# baseboard_rev_01.net
KiCad netlist of a schematic drawn in EAGLE
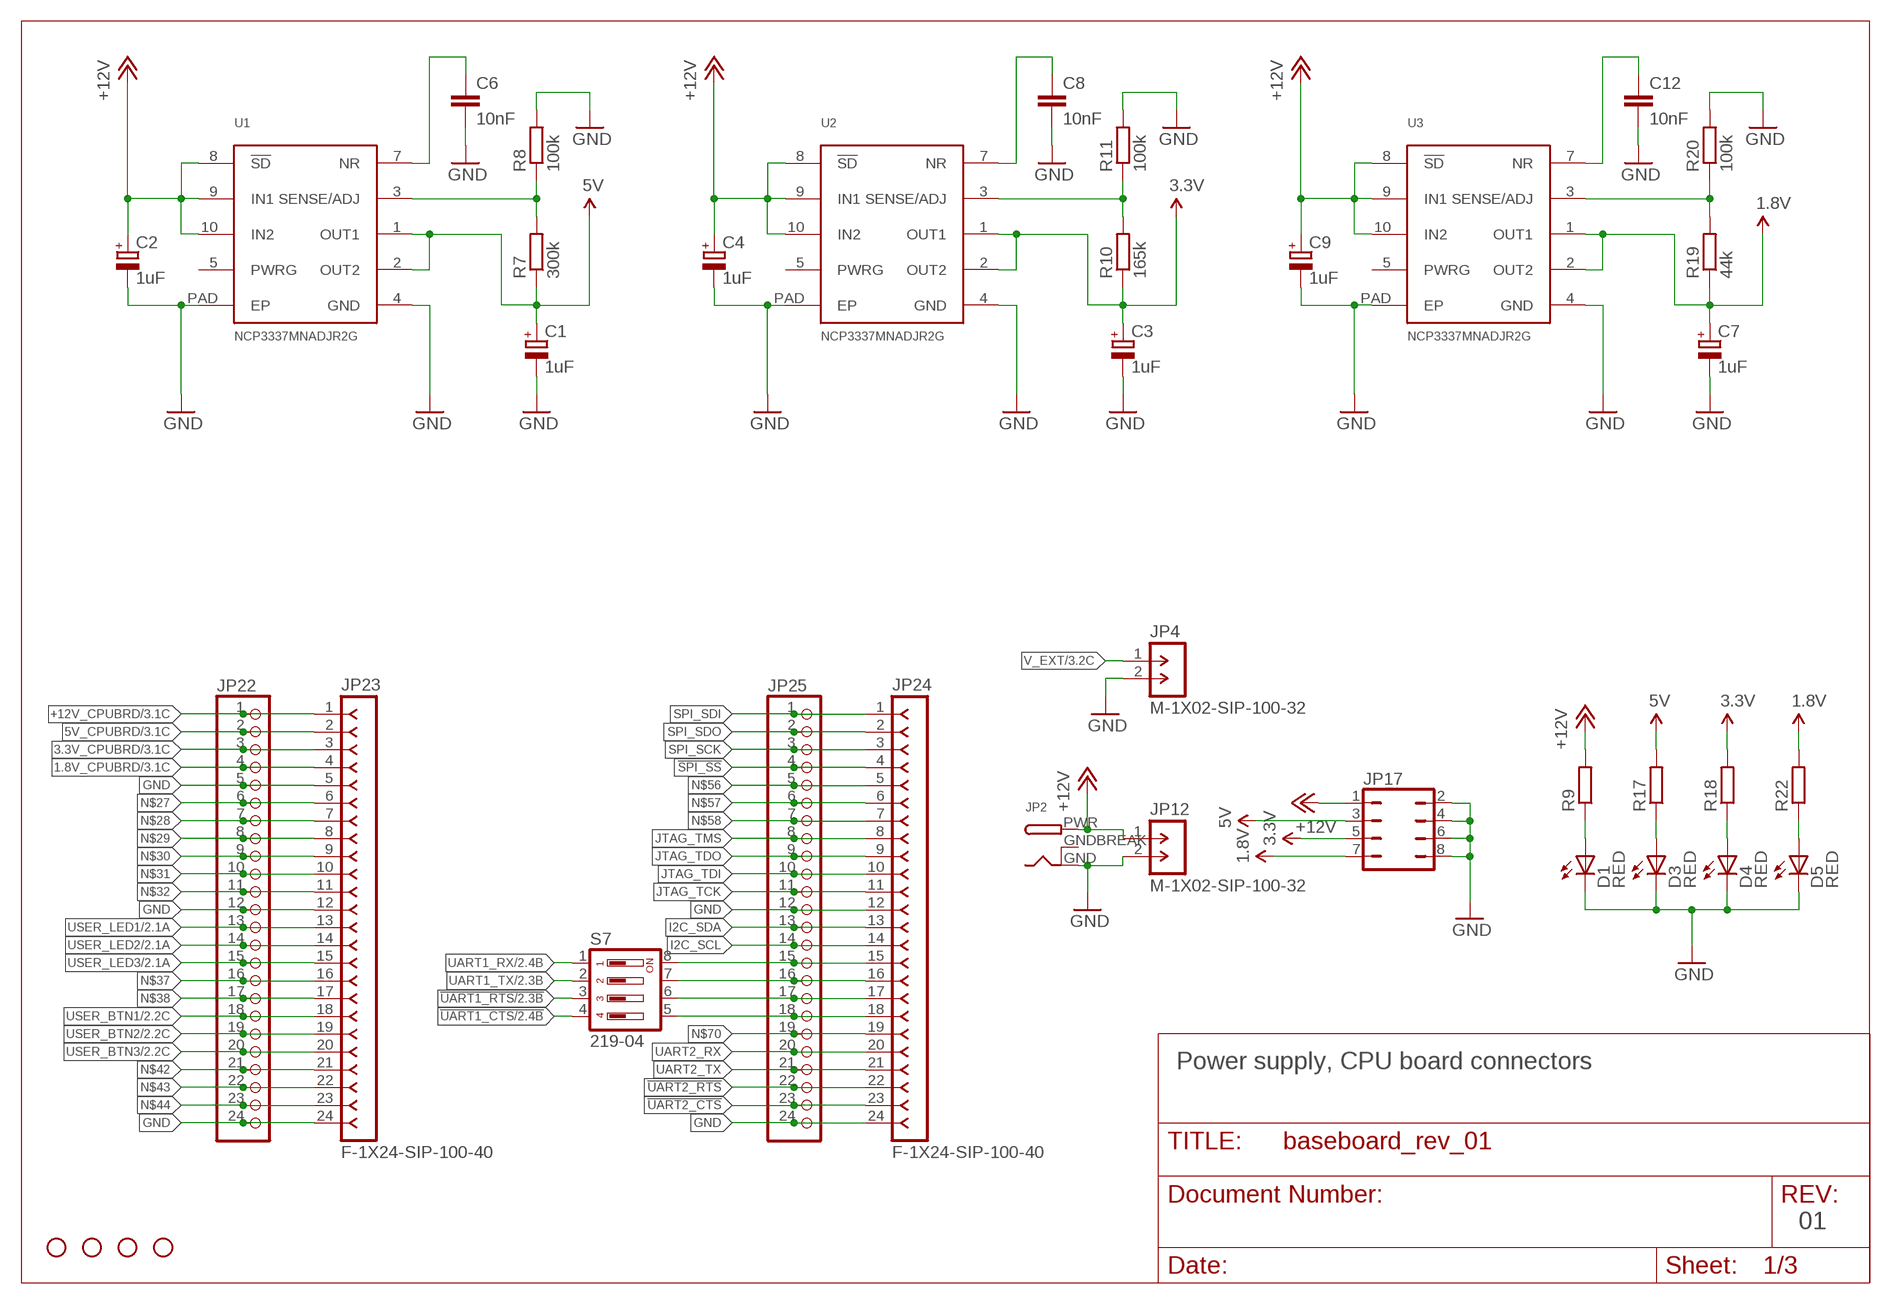
[diagram p0: schematic, sheet 1]
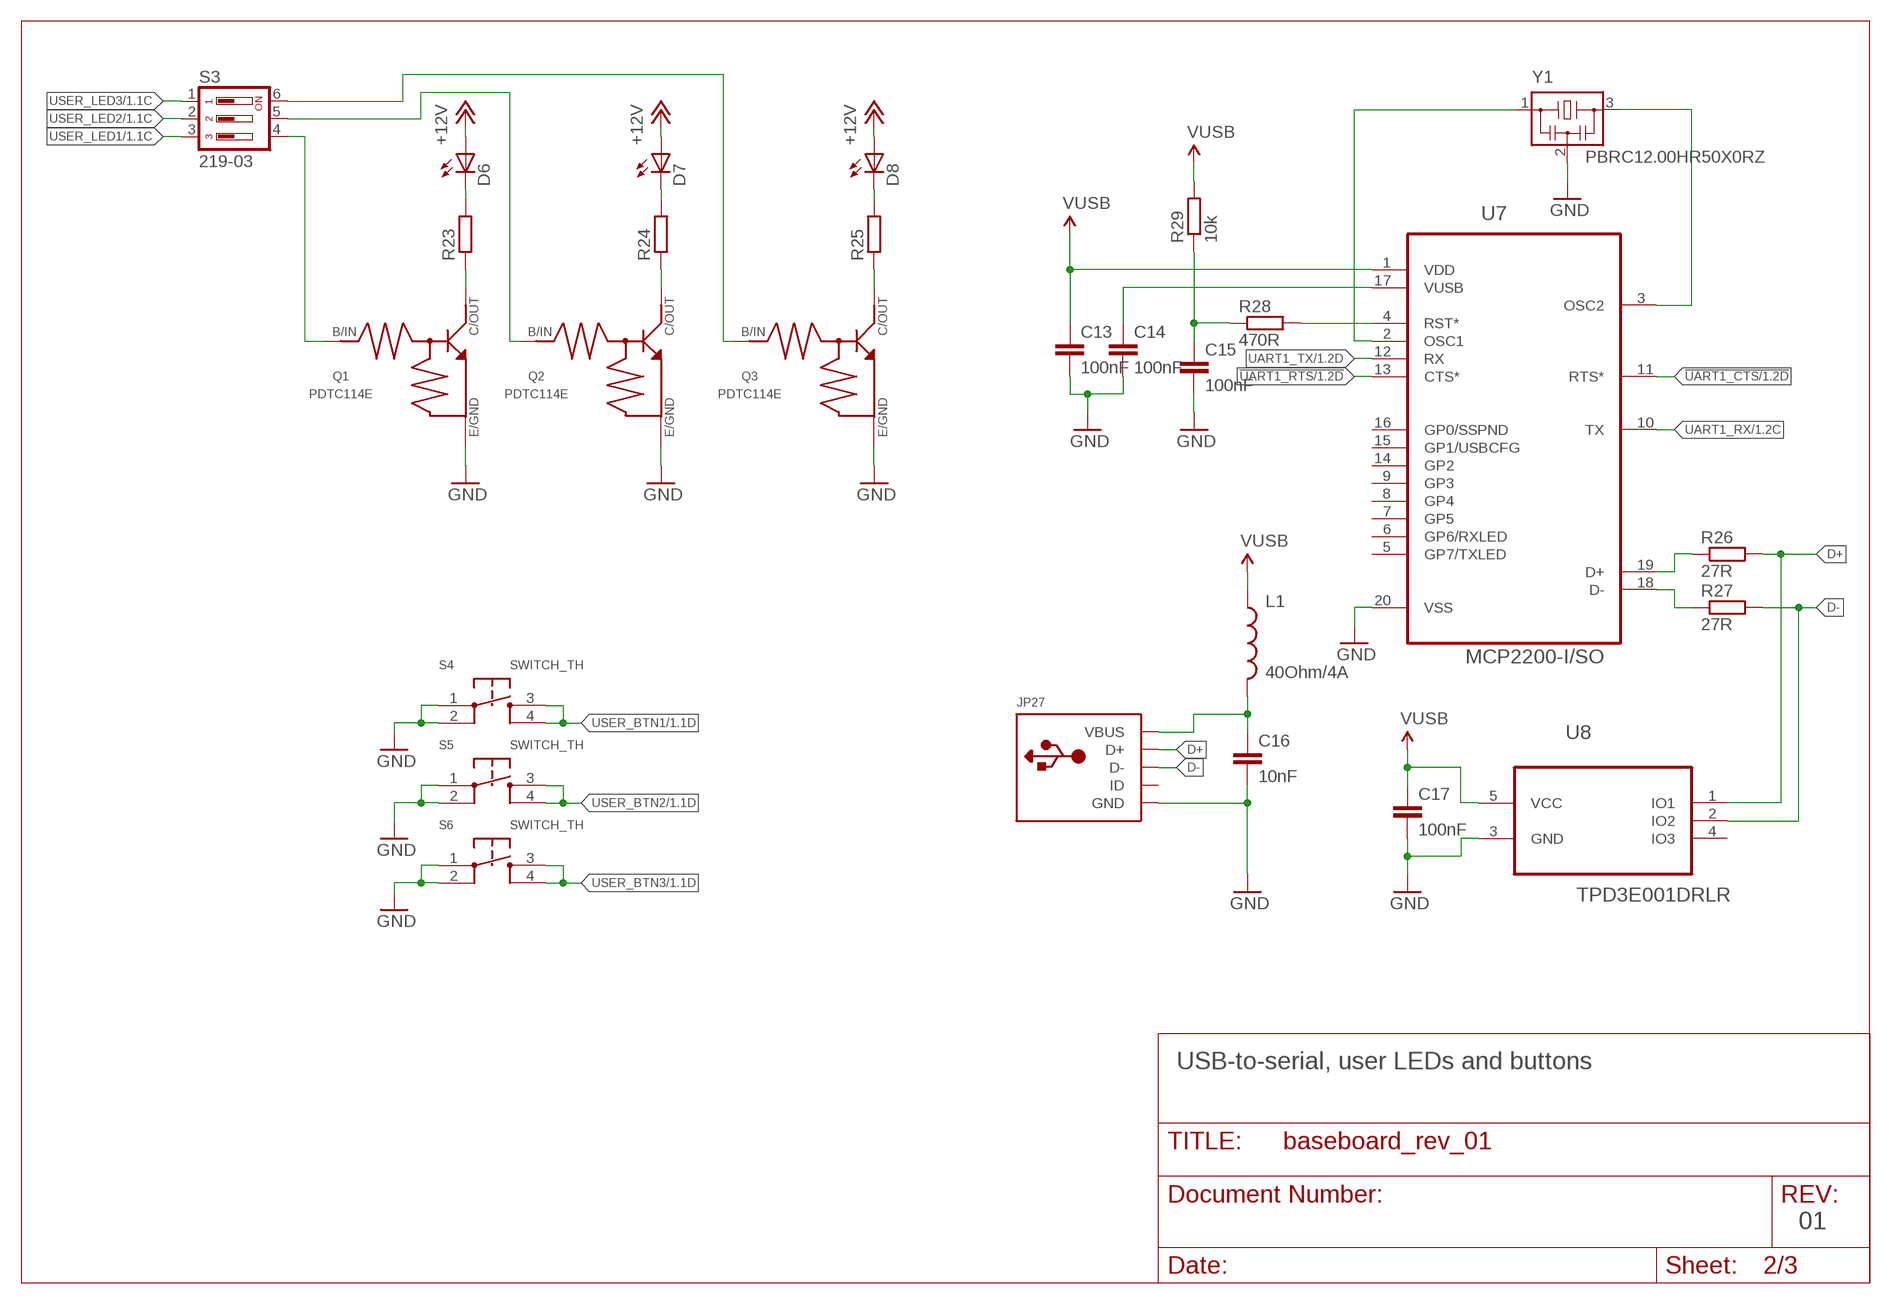
[diagram p1: schematic, sheet 2]
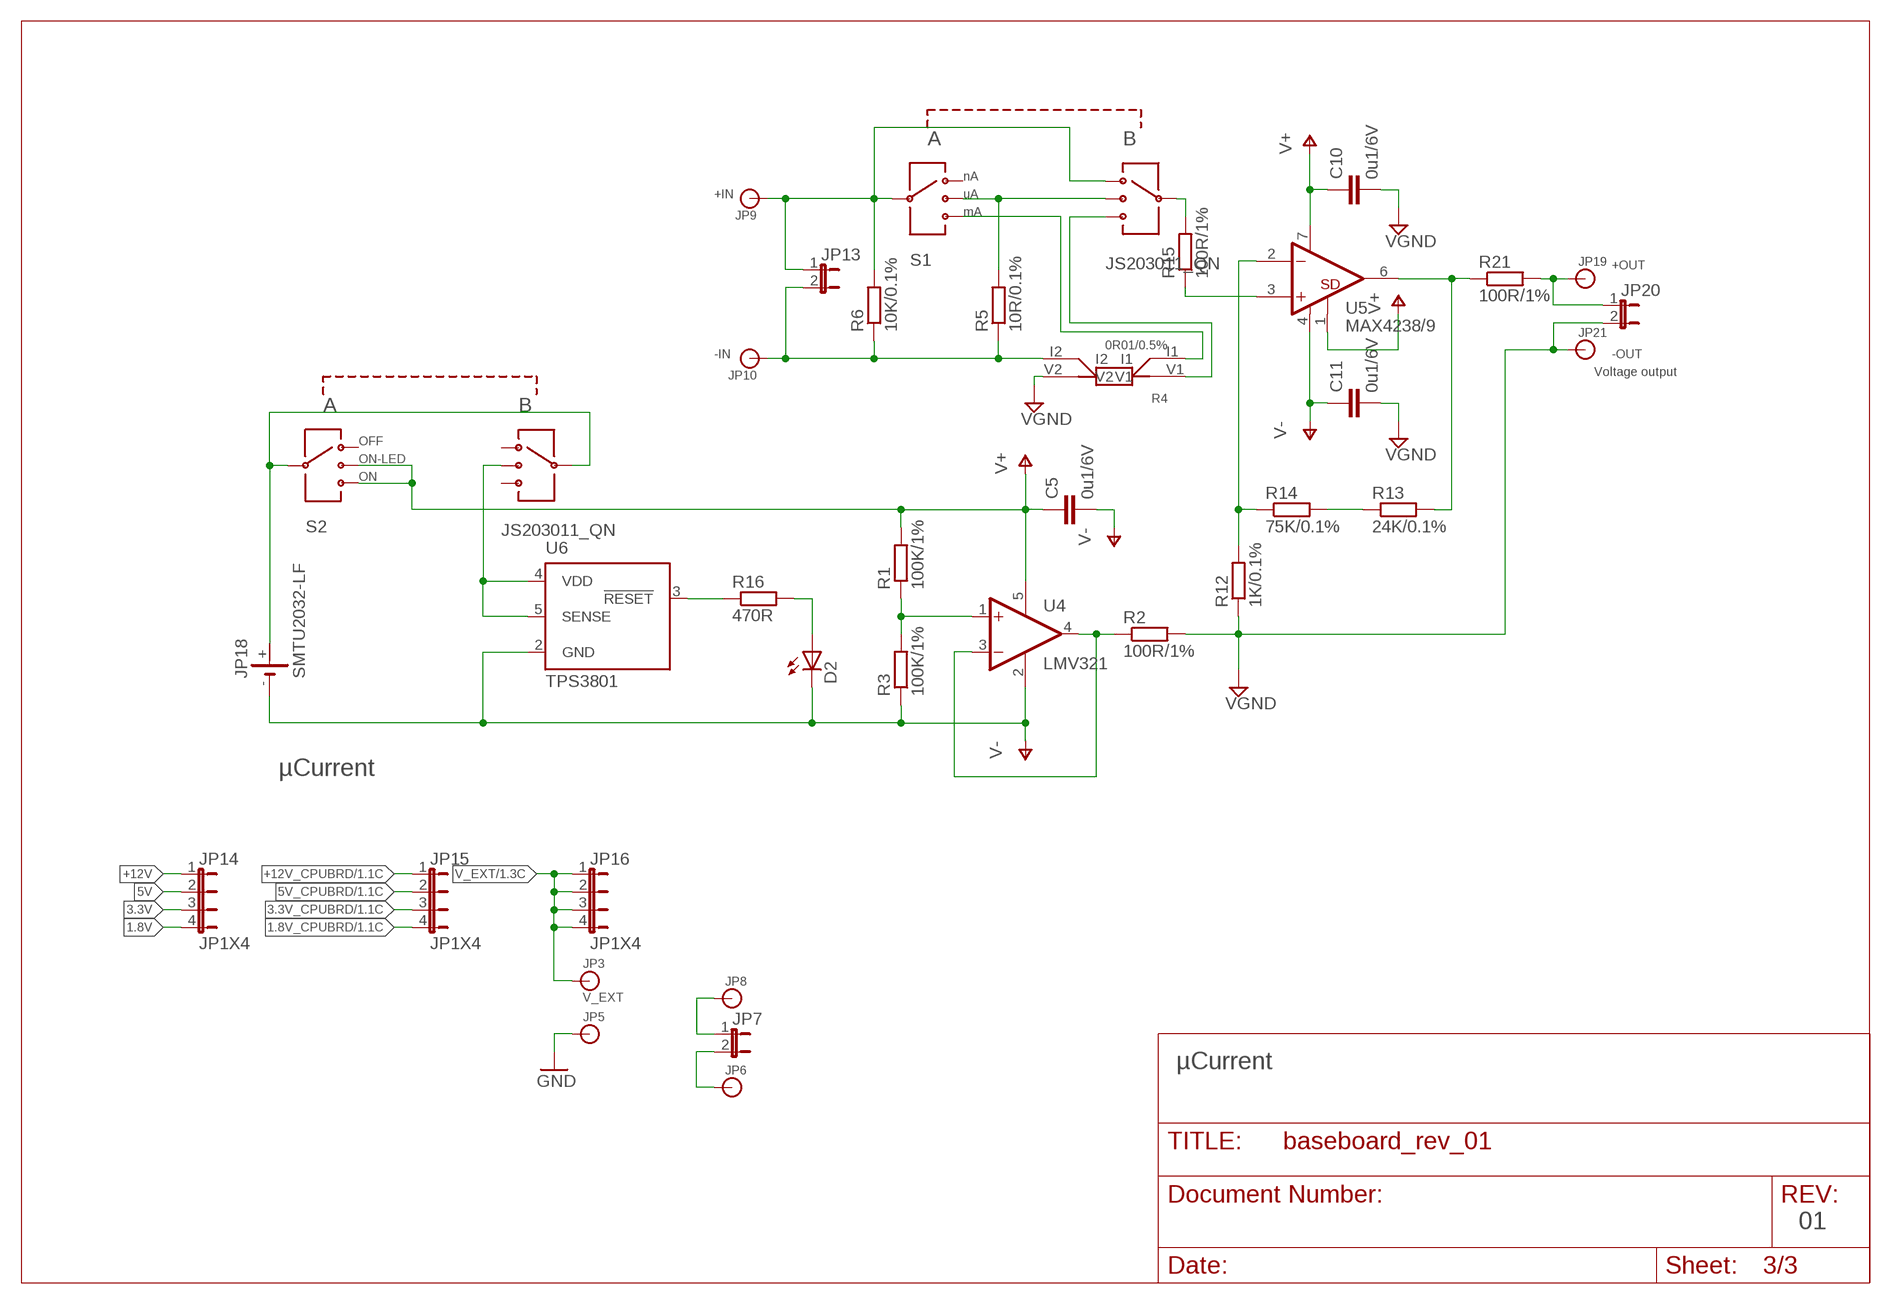
[diagram p2: schematic, sheet 3]

(export (version "E")
  (design (tool "Eeschema 10.0.6"))
  (components
    (comp (ref "C1")
      (value "1uF")
      (footprint "eagle-import:PANASONIC_B")
      (libsource (lib "eagle-import") (part "CPOL-EUB"))
    )
    (comp (ref "C2")
      (value "1uF")
      (footprint "eagle-import:PANASONIC_B")
      (libsource (lib "eagle-import") (part "CPOL-EUB"))
    )
    (comp (ref "C3")
      (value "1uF")
      (footprint "eagle-import:PANASONIC_B")
      (libsource (lib "eagle-import") (part "CPOL-EUB"))
    )
    (comp (ref "C4")
      (value "1uF")
      (footprint "eagle-import:PANASONIC_B")
      (libsource (lib "eagle-import") (part "CPOL-EUB"))
    )
    (comp (ref "C6")
      (value "10nF")
      (footprint "eagle-import:C0805")
      (libsource (lib "eagle-import") (part "C-EUC0805"))
    )
    (comp (ref "C7")
      (value "1uF")
      (footprint "eagle-import:PANASONIC_B")
      (libsource (lib "eagle-import") (part "CPOL-EUB"))
    )
    (comp (ref "C8")
      (value "10nF")
      (footprint "eagle-import:C0805")
      (libsource (lib "eagle-import") (part "C-EUC0805"))
    )
    (comp (ref "C9")
      (value "1uF")
      (footprint "eagle-import:PANASONIC_B")
      (libsource (lib "eagle-import") (part "CPOL-EUB"))
    )
    (comp (ref "C12")
      (value "10nF")
      (footprint "eagle-import:C0805")
      (libsource (lib "eagle-import") (part "C-EUC0805"))
    )
    (comp (ref "D1")
      (value "RED")
      (footprint "eagle-import:CHIPLED_0805")
      (libsource (lib "eagle-import") (part "LEDCHIPLED_0805"))
    )
    (comp (ref "D3")
      (value "RED")
      (footprint "eagle-import:CHIPLED_0805")
      (libsource (lib "eagle-import") (part "LEDCHIPLED_0805"))
    )
    (comp (ref "D4")
      (value "RED")
      (footprint "eagle-import:CHIPLED_0805")
      (libsource (lib "eagle-import") (part "LEDCHIPLED_0805"))
    )
    (comp (ref "D5")
      (value "RED")
      (footprint "eagle-import:CHIPLED_0805")
      (libsource (lib "eagle-import") (part "LEDCHIPLED_0805"))
    )
    (comp (ref "JP1")
      (value "STAND-OFF")
      (footprint "eagle-import:STAND-OFF")
      (libsource (lib "eagle-import") (part "STAND-OFF"))
    )
    (comp (ref "JP2")
      (value "DCBARRELPTH")
      (footprint "eagle-import:DCJACK_2MM_PTH")
      (libsource (lib "eagle-import") (part "DCBARRELPTH"))
    )
    (comp (ref "JP4")
      (value "M-1X02-SIP-100-32")
      (footprint "eagle-import:SIP-100-02-32")
      (libsource (lib "eagle-import") (part "M-1X02-SIP-100-32"))
    )
    (comp (ref "JP11")
      (value "STAND-OFF")
      (footprint "eagle-import:STAND-OFF")
      (libsource (lib "eagle-import") (part "STAND-OFF"))
    )
    (comp (ref "JP12")
      (value "M-1X02-SIP-100-32")
      (footprint "eagle-import:SIP-100-02-32")
      (libsource (lib "eagle-import") (part "M-1X02-SIP-100-32"))
    )
    (comp (ref "JP17")
      (value "JP4Q")
      (footprint "eagle-import:JP4Q")
      (libsource (lib "eagle-import") (part "JP4Q"))
    )
    (comp (ref "JP22")
      (value "PINHD-1X24")
      (footprint "eagle-import:1X24")
      (libsource (lib "eagle-import") (part "PINHD-1X24"))
    )
    (comp (ref "JP23")
      (value "F-1X24-SIP-100-40")
      (footprint "eagle-import:SIP-100-24-40")
      (libsource (lib "eagle-import") (part "F-1X24-SIP-100-40"))
    )
    (comp (ref "JP24")
      (value "F-1X24-SIP-100-40")
      (footprint "eagle-import:SIP-100-24-40")
      (libsource (lib "eagle-import") (part "F-1X24-SIP-100-40"))
    )
    (comp (ref "JP25")
      (value "PINHD-1X24")
      (footprint "eagle-import:1X24")
      (libsource (lib "eagle-import") (part "PINHD-1X24"))
    )
    (comp (ref "JP26")
      (value "STAND-OFF")
      (footprint "eagle-import:STAND-OFF")
      (libsource (lib "eagle-import") (part "STAND-OFF"))
    )
    (comp (ref "JP28")
      (value "STAND-OFF")
      (footprint "eagle-import:STAND-OFF")
      (libsource (lib "eagle-import") (part "STAND-OFF"))
    )
    (comp (ref "R7")
      (value "300k")
      (footprint "eagle-import:R0805")
      (libsource (lib "eagle-import") (part "R-EU_R0805"))
    )
    (comp (ref "R8")
      (value "100k")
      (footprint "eagle-import:R0805")
      (libsource (lib "eagle-import") (part "R-EU_R0805"))
    )
    (comp (ref "R9")
      (value "R-EU_R0805")
      (footprint "eagle-import:R0805")
      (libsource (lib "eagle-import") (part "R-EU_R0805"))
    )
    (comp (ref "R10")
      (value "165k")
      (footprint "eagle-import:R0805")
      (libsource (lib "eagle-import") (part "R-EU_R0805"))
    )
    (comp (ref "R11")
      (value "100k")
      (footprint "eagle-import:R0805")
      (libsource (lib "eagle-import") (part "R-EU_R0805"))
    )
    (comp (ref "R17")
      (value "R-EU_R0805")
      (footprint "eagle-import:R0805")
      (libsource (lib "eagle-import") (part "R-EU_R0805"))
    )
    (comp (ref "R18")
      (value "R-EU_R0805")
      (footprint "eagle-import:R0805")
      (libsource (lib "eagle-import") (part "R-EU_R0805"))
    )
    (comp (ref "R19")
      (value "44k")
      (footprint "eagle-import:R0805")
      (libsource (lib "eagle-import") (part "R-EU_R0805"))
    )
    (comp (ref "R20")
      (value "100k")
      (footprint "eagle-import:R0805")
      (libsource (lib "eagle-import") (part "R-EU_R0805"))
    )
    (comp (ref "R22")
      (value "R-EU_R0805")
      (footprint "eagle-import:R0805")
      (libsource (lib "eagle-import") (part "R-EU_R0805"))
    )
    (comp (ref "S7")
      (value "219-04")
      (footprint "eagle-import:CTS-219-04")
      (libsource (lib "eagle-import") (part "219-04"))
    )
    (comp (ref "U1")
      (value "NCP3337MNADJR2G")
      (footprint "eagle-import:DFN10")
      (libsource (lib "eagle-import") (part "NCP3337"))
    )
    (comp (ref "U2")
      (value "NCP3337MNADJR2G")
      (footprint "eagle-import:DFN10")
      (libsource (lib "eagle-import") (part "NCP3337"))
    )
    (comp (ref "U3")
      (value "NCP3337MNADJR2G")
      (footprint "eagle-import:DFN10")
      (libsource (lib "eagle-import") (part "NCP3337"))
    )
    (comp (ref "C5")
      (value "0u1/6V")
      (footprint "eagle-import:C0805K")
      (libsource (lib "eagle-import") (part "C-EUC0805K"))
    )
    (comp (ref "C10")
      (value "0u1/6V")
      (footprint "eagle-import:C0805K")
      (libsource (lib "eagle-import") (part "C-EUC0805K"))
    )
    (comp (ref "C11")
      (value "0u1/6V")
      (footprint "eagle-import:C0805K")
      (libsource (lib "eagle-import") (part "C-EUC0805K"))
    )
    (comp (ref "D2")
      (value "LEDCHIPLED_0805")
      (footprint "eagle-import:CHIPLED_0805")
      (libsource (lib "eagle-import") (part "LEDCHIPLED_0805"))
    )
    (comp (ref "JP3")
      (value "V_EXT")
      (footprint "eagle-import:BANANA_CONN")
      (libsource (lib "eagle-import") (part "BANANA_CONN"))
    )
    (comp (ref "JP5")
      (value "BANANA_CONN")
      (footprint "eagle-import:BANANA_CONN")
      (libsource (lib "eagle-import") (part "BANANA_CONN"))
    )
    (comp (ref "JP6")
      (value "BANANA_CONN")
      (footprint "eagle-import:BANANA_CONN")
      (libsource (lib "eagle-import") (part "BANANA_CONN"))
    )
    (comp (ref "JP7")
      (value "JUMPER-2PTH")
      (footprint "eagle-import:1X02")
      (libsource (lib "eagle-import") (part "JUMPER-2PTH"))
    )
    (comp (ref "JP8")
      (value "BANANA_CONN")
      (footprint "eagle-import:BANANA_CONN")
      (libsource (lib "eagle-import") (part "BANANA_CONN"))
    )
    (comp (ref "JP9")
      (value "BANANA_CONN")
      (footprint "eagle-import:BANANA_CONN")
      (libsource (lib "eagle-import") (part "BANANA_CONN"))
    )
    (comp (ref "JP10")
      (value "BANANA_CONN")
      (footprint "eagle-import:BANANA_CONN")
      (libsource (lib "eagle-import") (part "BANANA_CONN"))
    )
    (comp (ref "JP13")
      (value "JUMPER-2PTH")
      (footprint "eagle-import:1X02")
      (libsource (lib "eagle-import") (part "JUMPER-2PTH"))
    )
    (comp (ref "JP14")
      (value "JP1X4")
      (footprint "eagle-import:JP1X4")
      (libsource (lib "eagle-import") (part "JP1X4"))
    )
    (comp (ref "JP15")
      (value "JP1X4")
      (footprint "eagle-import:JP1X4")
      (libsource (lib "eagle-import") (part "JP1X4"))
    )
    (comp (ref "JP16")
      (value "JP1X4")
      (footprint "eagle-import:JP1X4")
      (libsource (lib "eagle-import") (part "JP1X4"))
    )
    (comp (ref "JP18")
      (value "SMTU2032-LF")
      (footprint "eagle-import:SMTU2032-LF")
      (libsource (lib "eagle-import") (part "SMTU2032-LF"))
    )
    (comp (ref "JP19")
      (value "BANANA_CONN")
      (footprint "eagle-import:BANANA_CONN")
      (libsource (lib "eagle-import") (part "BANANA_CONN"))
    )
    (comp (ref "JP20")
      (value "JUMPER-2PTH")
      (footprint "eagle-import:1X02")
      (libsource (lib "eagle-import") (part "JUMPER-2PTH"))
    )
    (comp (ref "JP21")
      (value "BANANA_CONN")
      (footprint "eagle-import:BANANA_CONN")
      (libsource (lib "eagle-import") (part "BANANA_CONN"))
    )
    (comp (ref "R1")
      (value "100K/1%")
      (footprint "eagle-import:R0805")
      (libsource (lib "eagle-import") (part "R-EU_R0805"))
    )
    (comp (ref "R2")
      (value "100R/1%")
      (footprint "eagle-import:R0805")
      (libsource (lib "eagle-import") (part "R-EU_R0805"))
    )
    (comp (ref "R3")
      (value "100K/1%")
      (footprint "eagle-import:R0805")
      (libsource (lib "eagle-import") (part "R-EU_R0805"))
    )
    (comp (ref "R4")
      (value "0R01/0.5%")
      (footprint "eagle-import:LVK12RXXXXXX")
      (libsource (lib "eagle-import") (part "LVKXXRXXXXXX"))
    )
    (comp (ref "R5")
      (value "10R/0.1%")
      (footprint "eagle-import:R0805")
      (libsource (lib "eagle-import") (part "R-EU_R0805"))
    )
    (comp (ref "R6")
      (value "10K/0.1%")
      (footprint "eagle-import:R0805")
      (libsource (lib "eagle-import") (part "R-EU_R0805"))
    )
    (comp (ref "R12")
      (value "1K/0.1%")
      (footprint "eagle-import:R0805")
      (libsource (lib "eagle-import") (part "R-EU_R0805"))
    )
    (comp (ref "R13")
      (value "24K/0.1%")
      (footprint "eagle-import:R0805")
      (libsource (lib "eagle-import") (part "R-EU_R0805"))
    )
    (comp (ref "R14")
      (value "75K/0.1%")
      (footprint "eagle-import:R0805")
      (libsource (lib "eagle-import") (part "R-EU_R0805"))
    )
    (comp (ref "R15")
      (value "100R/1%")
      (footprint "eagle-import:R0805")
      (libsource (lib "eagle-import") (part "R-EU_R0805"))
    )
    (comp (ref "R16")
      (value "470R")
      (footprint "eagle-import:R0805")
      (libsource (lib "eagle-import") (part "R-EU_R0805"))
    )
    (comp (ref "R21")
      (value "100R/1%")
      (footprint "eagle-import:R0805")
      (libsource (lib "eagle-import") (part "R-EU_R0805"))
    )
    (comp (ref "S1")
      (value "JS203011_QN")
      (footprint "eagle-import:JS203011")
      (libsource (lib "eagle-import") (part "JS203011_QN"))
    )
    (comp (ref "S2")
      (value "JS203011_QN")
      (footprint "eagle-import:JS203011")
      (libsource (lib "eagle-import") (part "JS203011_QN"))
    )
    (comp (ref "U4")
      (value "LMV321")
      (footprint "eagle-import:SC70-5L")
      (libsource (lib "eagle-import") (part "LMV321?M7"))
    )
    (comp (ref "U5")
      (value "MAX4238/9")
      (footprint "eagle-import:SO08")
      (libsource (lib "eagle-import") (part "MAX4238/9"))
    )
    (comp (ref "U6")
      (value "TPS3801")
      (footprint "eagle-import:DCK")
      (fields (field (name "MF") "TEXAS INSTRUMENTS") (field (name "MPN") "TPS3803-01DCKR"))
      (libsource (lib "eagle-import") (part "TPS3803-01"))
    )
    (comp (ref "C13")
      (value "100nF")
      (footprint "eagle-import:C0805")
      (libsource (lib "eagle-import") (part "C-EUC0805"))
    )
    (comp (ref "C14")
      (value "100nF")
      (footprint "eagle-import:C0805")
      (libsource (lib "eagle-import") (part "C-EUC0805"))
    )
    (comp (ref "C15")
      (value "100nF")
      (footprint "eagle-import:C0805")
      (libsource (lib "eagle-import") (part "C-EUC0805"))
    )
    (comp (ref "C16")
      (value "10nF")
      (footprint "eagle-import:C0805")
      (libsource (lib "eagle-import") (part "C-EUC0805"))
    )
    (comp (ref "C17")
      (value "100nF")
      (footprint "eagle-import:C0805")
      (libsource (lib "eagle-import") (part "C-EUC0805"))
    )
    (comp (ref "D6")
      (value "LEDCHIPLED_0805")
      (footprint "eagle-import:CHIPLED_0805")
      (libsource (lib "eagle-import") (part "LEDCHIPLED_0805"))
    )
    (comp (ref "D7")
      (value "LEDCHIPLED_0805")
      (footprint "eagle-import:CHIPLED_0805")
      (libsource (lib "eagle-import") (part "LEDCHIPLED_0805"))
    )
    (comp (ref "D8")
      (value "LEDCHIPLED_0805")
      (footprint "eagle-import:CHIPLED_0805")
      (libsource (lib "eagle-import") (part "LEDCHIPLED_0805"))
    )
    (comp (ref "JP27")
      (value "USBMINIB")
      (footprint "eagle-import:USB-MINIB")
      (libsource (lib "eagle-import") (part "USBMINIB"))
    )
    (comp (ref "L1")
      (value "40Ohm/4A")
      (footprint "eagle-import:0805")
      (libsource (lib "eagle-import") (part "INDUCTOR0805"))
    )
    (comp (ref "Q1")
      (value "PDTC114E")
      (footprint "eagle-import:SOT416")
      (libsource (lib "eagle-import") (part "PDTC114E"))
    )
    (comp (ref "Q2")
      (value "PDTC114E")
      (footprint "eagle-import:SOT416")
      (libsource (lib "eagle-import") (part "PDTC114E"))
    )
    (comp (ref "Q3")
      (value "PDTC114E")
      (footprint "eagle-import:SOT416")
      (libsource (lib "eagle-import") (part "PDTC114E"))
    )
    (comp (ref "R23")
      (value "R-EU_R0805")
      (footprint "eagle-import:R0805")
      (libsource (lib "eagle-import") (part "R-EU_R0805"))
    )
    (comp (ref "R24")
      (value "R-EU_R0805")
      (footprint "eagle-import:R0805")
      (libsource (lib "eagle-import") (part "R-EU_R0805"))
    )
    (comp (ref "R25")
      (value "R-EU_R0805")
      (footprint "eagle-import:R0805")
      (libsource (lib "eagle-import") (part "R-EU_R0805"))
    )
    (comp (ref "R26")
      (value "27R")
      (footprint "eagle-import:R0805")
      (libsource (lib "eagle-import") (part "R-EU_R0805"))
    )
    (comp (ref "R27")
      (value "27R")
      (footprint "eagle-import:R0805")
      (libsource (lib "eagle-import") (part "R-EU_R0805"))
    )
    (comp (ref "R28")
      (value "470R")
      (footprint "eagle-import:R0805")
      (libsource (lib "eagle-import") (part "R-EU_R0805"))
    )
    (comp (ref "R29")
      (value "10k")
      (footprint "eagle-import:R0805")
      (libsource (lib "eagle-import") (part "R-EU_R0805"))
    )
    (comp (ref "S3")
      (value "219-03")
      (footprint "eagle-import:CTS-219-03")
      (libsource (lib "eagle-import") (part "219-03"))
    )
    (comp (ref "S4")
      (value "SWITCH_TH")
      (footprint "eagle-import:SWITCH_TROUGHHOLE")
      (libsource (lib "eagle-import") (part "SWITCH_TH"))
    )
    (comp (ref "S5")
      (value "SWITCH_TH")
      (footprint "eagle-import:SWITCH_TROUGHHOLE")
      (libsource (lib "eagle-import") (part "SWITCH_TH"))
    )
    (comp (ref "S6")
      (value "SWITCH_TH")
      (footprint "eagle-import:SWITCH_TROUGHHOLE")
      (libsource (lib "eagle-import") (part "SWITCH_TH"))
    )
    (comp (ref "U7")
      (value "MCP2200-I/SO")
      (footprint "eagle-import:SOIC127P1034X264-20N")
      (libsource (lib "eagle-import") (part "MCP2200-I/SO"))
    )
    (comp (ref "U8")
      (value "TPD3E001DRLR")
      (footprint "eagle-import:SOT50P160X60-5N")
      (libsource (lib "eagle-import") (part "TPD3E001DRLR"))
    )
    (comp (ref "Y1")
      (value "PBRC12.00HR50X0RZ")
      (footprint "eagle-import:PBRC-H")
      (libsource (lib "eagle-import") (part "PBRC-X"))
    )
  )
  (nets
    (net (code "1") (name "+12V") (class "Default")
      (node (ref "C2") (pin "+") (pinfunction "+_+") (pintype "passive"))
      (node (ref "C4") (pin "+") (pinfunction "+_+") (pintype "passive"))
      (node (ref "C9") (pin "+") (pinfunction "+_+") (pintype "passive"))
      (node (ref "D6") (pin "A") (pinfunction "A_A") (pintype "passive"))
      (node (ref "D7") (pin "A") (pinfunction "A_A") (pintype "passive"))
      (node (ref "D8") (pin "A") (pinfunction "A_A") (pintype "passive"))
      (node (ref "JP12") (pin "1") (pinfunction "1_1") (pintype "passive"))
      (node (ref "JP14") (pin "1") (pinfunction "1_1") (pintype "passive"))
      (node (ref "JP17") (pin "1") (pinfunction "1_1") (pintype "passive"))
      (node (ref "JP2") (pin "PWR") (pinfunction "PWR_PWR") (pintype "power_in"))
      (node (ref "R9") (pin "2") (pinfunction "2_2") (pintype "passive"))
      (node (ref "U1") (pin "10") (pinfunction "IN2_10") (pintype "bidirectional"))
      (node (ref "U1") (pin "8") (pinfunction "~{SD}_8") (pintype "bidirectional"))
      (node (ref "U1") (pin "9") (pinfunction "IN1_9") (pintype "bidirectional"))
      (node (ref "U2") (pin "10") (pinfunction "IN2_10") (pintype "bidirectional"))
      (node (ref "U2") (pin "8") (pinfunction "~{SD}_8") (pintype "bidirectional"))
      (node (ref "U2") (pin "9") (pinfunction "IN1_9") (pintype "bidirectional"))
      (node (ref "U3") (pin "10") (pinfunction "IN2_10") (pintype "bidirectional"))
      (node (ref "U3") (pin "8") (pinfunction "~{SD}_8") (pintype "bidirectional"))
      (node (ref "U3") (pin "9") (pinfunction "IN1_9") (pintype "bidirectional"))
    )
    (net (code "2") (name "+12V_CPUBRD") (class "Default")
      (node (ref "JP15") (pin "1") (pinfunction "1_1") (pintype "passive"))
      (node (ref "JP22") (pin "1") (pinfunction "1_1") (pintype "passive"))
      (node (ref "JP23") (pin "1") (pinfunction "1_1") (pintype "passive"))
    )
    (net (code "3") (name "1.8V") (class "Default")
      (node (ref "C7") (pin "+") (pinfunction "+_+") (pintype "passive"))
      (node (ref "JP14") (pin "4") (pinfunction "4_4") (pintype "passive"))
      (node (ref "JP17") (pin "7") (pinfunction "7_7") (pintype "passive"))
      (node (ref "R19") (pin "1") (pinfunction "1_1") (pintype "passive"))
      (node (ref "R22") (pin "2") (pinfunction "2_2") (pintype "passive"))
      (node (ref "U3") (pin "1") (pinfunction "OUT1_1") (pintype "bidirectional"))
      (node (ref "U3") (pin "2") (pinfunction "OUT2_2") (pintype "bidirectional"))
    )
    (net (code "4") (name "1.8V_CPUBRD") (class "Default")
      (node (ref "JP15") (pin "4") (pinfunction "4_4") (pintype "passive"))
      (node (ref "JP22") (pin "4") (pinfunction "4_4") (pintype "passive"))
      (node (ref "JP23") (pin "4") (pinfunction "4_4") (pintype "passive"))
    )
    (net (code "5") (name "3.3V") (class "Default")
      (node (ref "C3") (pin "+") (pinfunction "+_+") (pintype "passive"))
      (node (ref "JP14") (pin "3") (pinfunction "3_3") (pintype "passive"))
      (node (ref "JP17") (pin "5") (pinfunction "5_5") (pintype "passive"))
      (node (ref "R10") (pin "1") (pinfunction "1_1") (pintype "passive"))
      (node (ref "R18") (pin "2") (pinfunction "2_2") (pintype "passive"))
      (node (ref "U2") (pin "1") (pinfunction "OUT1_1") (pintype "bidirectional"))
      (node (ref "U2") (pin "2") (pinfunction "OUT2_2") (pintype "bidirectional"))
    )
    (net (code "6") (name "3.3V_CPUBRD") (class "Default")
      (node (ref "JP15") (pin "3") (pinfunction "3_3") (pintype "passive"))
      (node (ref "JP22") (pin "3") (pinfunction "3_3") (pintype "passive"))
      (node (ref "JP23") (pin "3") (pinfunction "3_3") (pintype "passive"))
    )
    (net (code "7") (name "5V") (class "Default")
      (node (ref "C1") (pin "+") (pinfunction "+_+") (pintype "passive"))
      (node (ref "JP14") (pin "2") (pinfunction "2_2") (pintype "passive"))
      (node (ref "JP17") (pin "3") (pinfunction "3_3") (pintype "passive"))
      (node (ref "R17") (pin "2") (pinfunction "2_2") (pintype "passive"))
      (node (ref "R7") (pin "1") (pinfunction "1_1") (pintype "passive"))
      (node (ref "U1") (pin "1") (pinfunction "OUT1_1") (pintype "bidirectional"))
      (node (ref "U1") (pin "2") (pinfunction "OUT2_2") (pintype "bidirectional"))
    )
    (net (code "8") (name "5V_CPUBRD") (class "Default")
      (node (ref "JP15") (pin "2") (pinfunction "2_2") (pintype "passive"))
      (node (ref "JP22") (pin "2") (pinfunction "2_2") (pintype "passive"))
      (node (ref "JP23") (pin "2") (pinfunction "2_2") (pintype "passive"))
    )
    (net (code "9") (name "D+") (class "Default")
      (node (ref "JP27") (pin "D+") (pinfunction "D+_D+") (pintype "bidirectional"))
      (node (ref "R26") (pin "2") (pinfunction "2_2") (pintype "passive"))
      (node (ref "U8") (pin "1") (pinfunction "IO1_1") (pintype "bidirectional"))
    )
    (net (code "10") (name "D-") (class "Default")
      (node (ref "JP27") (pin "D-") (pinfunction "D-_D-") (pintype "bidirectional"))
      (node (ref "R27") (pin "2") (pinfunction "2_2") (pintype "passive"))
      (node (ref "U8") (pin "2") (pinfunction "IO2_2") (pintype "bidirectional"))
    )
    (net (code "11") (name "GND") (class "Default")
      (node (ref "C1") (pin "-") (pinfunction "-_-") (pintype "passive"))
      (node (ref "C12") (pin "2") (pinfunction "2_2") (pintype "passive"))
      (node (ref "C13") (pin "2") (pinfunction "2_2") (pintype "passive"))
      (node (ref "C14") (pin "2") (pinfunction "2_2") (pintype "passive"))
      (node (ref "C15") (pin "2") (pinfunction "2_2") (pintype "passive"))
      (node (ref "C16") (pin "2") (pinfunction "2_2") (pintype "passive"))
      (node (ref "C17") (pin "2") (pinfunction "2_2") (pintype "passive"))
      (node (ref "C2") (pin "-") (pinfunction "-_-") (pintype "passive"))
      (node (ref "C3") (pin "-") (pinfunction "-_-") (pintype "passive"))
      (node (ref "C4") (pin "-") (pinfunction "-_-") (pintype "passive"))
      (node (ref "C6") (pin "2") (pinfunction "2_2") (pintype "passive"))
      (node (ref "C7") (pin "-") (pinfunction "-_-") (pintype "passive"))
      (node (ref "C8") (pin "2") (pinfunction "2_2") (pintype "passive"))
      (node (ref "C9") (pin "-") (pinfunction "-_-") (pintype "passive"))
      (node (ref "D1") (pin "C") (pinfunction "C_C") (pintype "passive"))
      (node (ref "D3") (pin "C") (pinfunction "C_C") (pintype "passive"))
      (node (ref "D4") (pin "C") (pinfunction "C_C") (pintype "passive"))
      (node (ref "D5") (pin "C") (pinfunction "C_C") (pintype "passive"))
      (node (ref "JP12") (pin "2") (pinfunction "2_2") (pintype "passive"))
      (node (ref "JP17") (pin "2") (pinfunction "2_2") (pintype "passive"))
      (node (ref "JP17") (pin "4") (pinfunction "4_4") (pintype "passive"))
      (node (ref "JP17") (pin "6") (pinfunction "6_6") (pintype "passive"))
      (node (ref "JP17") (pin "8") (pinfunction "8_8") (pintype "passive"))
      (node (ref "JP2") (pin "GND") (pinfunction "GND_GND") (pintype "power_in"))
      (node (ref "JP22") (pin "12") (pinfunction "12_12") (pintype "passive"))
      (node (ref "JP22") (pin "24") (pinfunction "24_24") (pintype "passive"))
      (node (ref "JP22") (pin "5") (pinfunction "5_5") (pintype "passive"))
      (node (ref "JP23") (pin "12") (pinfunction "12_12") (pintype "passive"))
      (node (ref "JP23") (pin "24") (pinfunction "24_24") (pintype "passive"))
      (node (ref "JP23") (pin "5") (pinfunction "5_5") (pintype "passive"))
      (node (ref "JP24") (pin "12") (pinfunction "12_12") (pintype "passive"))
      (node (ref "JP24") (pin "24") (pinfunction "24_24") (pintype "passive"))
      (node (ref "JP25") (pin "12") (pinfunction "12_12") (pintype "passive"))
      (node (ref "JP25") (pin "24") (pinfunction "24_24") (pintype "passive"))
      (node (ref "JP27") (pin "GND") (pinfunction "GND_GND") (pintype "power_in"))
      (node (ref "JP4") (pin "2") (pinfunction "2_2") (pintype "passive"))
      (node (ref "JP5") (pin "P$1") (pinfunction "1_P$1") (pintype "passive"))
      (node (ref "Q1") (pin "2") (pinfunction "E_2") (pintype "bidirectional"))
      (node (ref "Q2") (pin "2") (pinfunction "E_2") (pintype "bidirectional"))
      (node (ref "Q3") (pin "2") (pinfunction "E_2") (pintype "bidirectional"))
      (node (ref "R11") (pin "2") (pinfunction "2_2") (pintype "passive"))
      (node (ref "R20") (pin "2") (pinfunction "2_2") (pintype "passive"))
      (node (ref "R8") (pin "2") (pinfunction "2_2") (pintype "passive"))
      (node (ref "S4") (pin "1") (pintype "bidirectional"))
      (node (ref "S4") (pin "2") (pintype "bidirectional"))
      (node (ref "S5") (pin "1") (pintype "bidirectional"))
      (node (ref "S5") (pin "2") (pintype "bidirectional"))
      (node (ref "S6") (pin "1") (pintype "bidirectional"))
      (node (ref "S6") (pin "2") (pintype "bidirectional"))
      (node (ref "U1") (pin "4") (pinfunction "GND_4") (pintype "bidirectional"))
      (node (ref "U1") (pin "PAD") (pinfunction "EP_PAD") (pintype "bidirectional"))
      (node (ref "U2") (pin "4") (pinfunction "GND_4") (pintype "bidirectional"))
      (node (ref "U2") (pin "PAD") (pinfunction "EP_PAD") (pintype "bidirectional"))
      (node (ref "U3") (pin "4") (pinfunction "GND_4") (pintype "bidirectional"))
      (node (ref "U3") (pin "PAD") (pinfunction "EP_PAD") (pintype "bidirectional"))
      (node (ref "U7") (pin "20") (pinfunction "VSS_20") (pintype "power_in"))
      (node (ref "U8") (pin "3") (pinfunction "GND_3") (pintype "passive"))
      (node (ref "Y1") (pin "2") (pinfunction "2_2") (pintype "passive"))
    )
    (net (code "12") (name "GNDBREAK") (class "Default")
      (node (ref "JP2") (pin "GNDBREAK") (pinfunction "GNDBREAK_GNDBREAK") (pintype "power_in"))
    )
    (net (code "13") (name "I2C_SCL") (class "Default")
      (node (ref "JP24") (pin "14") (pinfunction "14_14") (pintype "passive"))
      (node (ref "JP25") (pin "14") (pinfunction "14_14") (pintype "passive"))
    )
    (net (code "14") (name "I2C_SDA") (class "Default")
      (node (ref "JP24") (pin "13") (pinfunction "13_13") (pintype "passive"))
      (node (ref "JP25") (pin "13") (pinfunction "13_13") (pintype "passive"))
    )
    (net (code "15") (name "JTAG_TCK") (class "Default")
      (node (ref "JP24") (pin "11") (pinfunction "11_11") (pintype "passive"))
      (node (ref "JP25") (pin "11") (pinfunction "11_11") (pintype "passive"))
    )
    (net (code "16") (name "JTAG_TDI") (class "Default")
      (node (ref "JP24") (pin "10") (pinfunction "10_10") (pintype "passive"))
      (node (ref "JP25") (pin "10") (pinfunction "10_10") (pintype "passive"))
    )
    (net (code "17") (name "JTAG_TDO") (class "Default")
      (node (ref "JP24") (pin "9") (pinfunction "9_9") (pintype "passive"))
      (node (ref "JP25") (pin "9") (pinfunction "9_9") (pintype "passive"))
    )
    (net (code "18") (name "JTAG_TMS") (class "Default")
      (node (ref "JP24") (pin "8") (pinfunction "8_8") (pintype "passive"))
      (node (ref "JP25") (pin "8") (pinfunction "8_8") (pintype "passive"))
    )
    (net (code "19") (name "N$27") (class "Default")
      (node (ref "JP22") (pin "6") (pinfunction "6_6") (pintype "passive"))
      (node (ref "JP23") (pin "6") (pinfunction "6_6") (pintype "passive"))
    )
    (net (code "20") (name "N$28") (class "Default")
      (node (ref "JP22") (pin "7") (pinfunction "7_7") (pintype "passive"))
      (node (ref "JP23") (pin "7") (pinfunction "7_7") (pintype "passive"))
    )
    (net (code "21") (name "N$29") (class "Default")
      (node (ref "JP22") (pin "8") (pinfunction "8_8") (pintype "passive"))
      (node (ref "JP23") (pin "8") (pinfunction "8_8") (pintype "passive"))
    )
    (net (code "22") (name "N$30") (class "Default")
      (node (ref "JP22") (pin "9") (pinfunction "9_9") (pintype "passive"))
      (node (ref "JP23") (pin "9") (pinfunction "9_9") (pintype "passive"))
    )
    (net (code "23") (name "N$31") (class "Default")
      (node (ref "JP22") (pin "10") (pinfunction "10_10") (pintype "passive"))
      (node (ref "JP23") (pin "10") (pinfunction "10_10") (pintype "passive"))
    )
    (net (code "24") (name "N$32") (class "Default")
      (node (ref "JP22") (pin "11") (pinfunction "11_11") (pintype "passive"))
      (node (ref "JP23") (pin "11") (pinfunction "11_11") (pintype "passive"))
    )
    (net (code "25") (name "N$37") (class "Default")
      (node (ref "JP22") (pin "16") (pinfunction "16_16") (pintype "passive"))
      (node (ref "JP23") (pin "16") (pinfunction "16_16") (pintype "passive"))
    )
    (net (code "26") (name "N$38") (class "Default")
      (node (ref "JP22") (pin "17") (pinfunction "17_17") (pintype "passive"))
      (node (ref "JP23") (pin "17") (pinfunction "17_17") (pintype "passive"))
    )
    (net (code "27") (name "N$42") (class "Default")
      (node (ref "JP22") (pin "21") (pinfunction "21_21") (pintype "passive"))
      (node (ref "JP23") (pin "21") (pinfunction "21_21") (pintype "passive"))
    )
    (net (code "28") (name "N$43") (class "Default")
      (node (ref "JP22") (pin "22") (pinfunction "22_22") (pintype "passive"))
      (node (ref "JP23") (pin "22") (pinfunction "22_22") (pintype "passive"))
    )
    (net (code "29") (name "N$44") (class "Default")
      (node (ref "JP22") (pin "23") (pinfunction "23_23") (pintype "passive"))
      (node (ref "JP23") (pin "23") (pinfunction "23_23") (pintype "passive"))
    )
    (net (code "30") (name "N$56") (class "Default")
      (node (ref "JP24") (pin "5") (pinfunction "5_5") (pintype "passive"))
      (node (ref "JP25") (pin "5") (pinfunction "5_5") (pintype "passive"))
    )
    (net (code "31") (name "N$57") (class "Default")
      (node (ref "JP24") (pin "6") (pinfunction "6_6") (pintype "passive"))
      (node (ref "JP25") (pin "6") (pinfunction "6_6") (pintype "passive"))
    )
    (net (code "32") (name "N$58") (class "Default")
      (node (ref "JP24") (pin "7") (pinfunction "7_7") (pintype "passive"))
      (node (ref "JP25") (pin "7") (pinfunction "7_7") (pintype "passive"))
    )
    (net (code "33") (name "N$70") (class "Default")
      (node (ref "JP24") (pin "19") (pinfunction "19_19") (pintype "passive"))
      (node (ref "JP25") (pin "19") (pinfunction "19_19") (pintype "passive"))
    )
    (net (code "34") (name "Net-(C15-Pad1)") (class "Default")
      (node (ref "C15") (pin "1") (pinfunction "1_1") (pintype "passive"))
      (node (ref "R28") (pin "1") (pinfunction "1_1") (pintype "passive"))
      (node (ref "R29") (pin "1") (pinfunction "1_1") (pintype "passive"))
    )
    (net (code "35") (name "Net-(C16-Pad1)") (class "Default")
      (node (ref "C16") (pin "1") (pinfunction "1_1") (pintype "passive"))
      (node (ref "JP27") (pin "VBUS") (pinfunction "VBUS_VBUS") (pintype "power_in"))
      (node (ref "L1") (pin "2") (pinfunction "2_2") (pintype "passive"))
    )
    (net (code "36") (name "Net-(D1-PadA)") (class "Default")
      (node (ref "D1") (pin "A") (pinfunction "A_A") (pintype "passive"))
      (node (ref "R9") (pin "1") (pinfunction "1_1") (pintype "passive"))
    )
    (net (code "37") (name "Net-(D2-PadA)") (class "Default")
      (node (ref "D2") (pin "A") (pinfunction "A_A") (pintype "passive"))
      (node (ref "R16") (pin "2") (pinfunction "2_2") (pintype "passive"))
    )
    (net (code "38") (name "Net-(D3-PadA)") (class "Default")
      (node (ref "D3") (pin "A") (pinfunction "A_A") (pintype "passive"))
      (node (ref "R17") (pin "1") (pinfunction "1_1") (pintype "passive"))
    )
    (net (code "39") (name "Net-(D4-PadA)") (class "Default")
      (node (ref "D4") (pin "A") (pinfunction "A_A") (pintype "passive"))
      (node (ref "R18") (pin "1") (pinfunction "1_1") (pintype "passive"))
    )
    (net (code "40") (name "Net-(D5-PadA)") (class "Default")
      (node (ref "D5") (pin "A") (pinfunction "A_A") (pintype "passive"))
      (node (ref "R22") (pin "1") (pinfunction "1_1") (pintype "passive"))
    )
    (net (code "41") (name "Net-(D6-PadC)") (class "Default")
      (node (ref "D6") (pin "C") (pinfunction "C_C") (pintype "passive"))
      (node (ref "R23") (pin "2") (pinfunction "2_2") (pintype "passive"))
    )
    (net (code "42") (name "Net-(D7-PadC)") (class "Default")
      (node (ref "D7") (pin "C") (pinfunction "C_C") (pintype "passive"))
      (node (ref "R24") (pin "2") (pinfunction "2_2") (pintype "passive"))
    )
    (net (code "43") (name "Net-(D8-PadC)") (class "Default")
      (node (ref "D8") (pin "C") (pinfunction "C_C") (pintype "passive"))
      (node (ref "R25") (pin "2") (pinfunction "2_2") (pintype "passive"))
    )
    (net (code "44") (name "Net-(JP6-1)") (class "Default")
      (node (ref "JP6") (pin "P$1") (pinfunction "1_P$1") (pintype "passive"))
      (node (ref "JP7") (pin "2") (pinfunction "2_2") (pintype "passive"))
    )
    (net (code "45") (name "Net-(JP8-1)") (class "Default")
      (node (ref "JP7") (pin "1") (pinfunction "1_1") (pintype "passive"))
      (node (ref "JP8") (pin "P$1") (pinfunction "1_P$1") (pintype "passive"))
    )
    (net (code "46") (name "Net-(JP9-1)") (class "Default")
      (node (ref "JP13") (pin "1") (pinfunction "1_1") (pintype "passive"))
      (node (ref "JP9") (pin "P$1") (pinfunction "1_P$1") (pintype "passive"))
      (node (ref "R6") (pin "2") (pinfunction "2_2") (pintype "passive"))
      (node (ref "S1") (pin "3") (pinfunction "3_3") (pintype "bidirectional"))
      (node (ref "S1") (pin "5") (pinfunction "5_5") (pintype "bidirectional"))
    )
    (net (code "47") (name "Net-(JP10-1)") (class "Default")
      (node (ref "JP10") (pin "P$1") (pinfunction "1_P$1") (pintype "passive"))
      (node (ref "JP13") (pin "2") (pinfunction "2_2") (pintype "passive"))
      (node (ref "R4") (pin "I2") (pinfunction "I2_I2") (pintype "bidirectional"))
      (node (ref "R5") (pin "1") (pinfunction "1_1") (pintype "passive"))
      (node (ref "R6") (pin "1") (pinfunction "1_1") (pintype "passive"))
    )
    (net (code "48") (name "Net-(JP18-Pad+)") (class "Default")
      (node (ref "JP18") (pin "+") (pinfunction "+_+") (pintype "passive"))
      (node (ref "S2") (pin "3") (pinfunction "3_3") (pintype "bidirectional"))
      (node (ref "S2") (pin "7") (pinfunction "7_7") (pintype "bidirectional"))
    )
    (net (code "49") (name "Net-(JP19-1)") (class "Default")
      (node (ref "JP19") (pin "P$1") (pinfunction "1_P$1") (pintype "passive"))
      (node (ref "JP20") (pin "1") (pinfunction "1_1") (pintype "passive"))
      (node (ref "R21") (pin "2") (pinfunction "2_2") (pintype "passive"))
    )
    (net (code "50") (name "Net-(JP24-Pad15)") (class "Default")
      (node (ref "JP24") (pin "15") (pinfunction "15_15") (pintype "passive"))
      (node (ref "JP25") (pin "15") (pinfunction "15_15") (pintype "passive"))
      (node (ref "S7") (pin "8") (pinfunction "8_8") (pintype "passive"))
    )
    (net (code "51") (name "Net-(JP24-Pad16)") (class "Default")
      (node (ref "JP24") (pin "16") (pinfunction "16_16") (pintype "passive"))
      (node (ref "JP25") (pin "16") (pinfunction "16_16") (pintype "passive"))
      (node (ref "S7") (pin "7") (pinfunction "7_7") (pintype "passive"))
    )
    (net (code "52") (name "Net-(JP24-Pad17)") (class "Default")
      (node (ref "JP24") (pin "17") (pinfunction "17_17") (pintype "passive"))
      (node (ref "JP25") (pin "17") (pinfunction "17_17") (pintype "passive"))
      (node (ref "S7") (pin "6") (pinfunction "6_6") (pintype "passive"))
    )
    (net (code "53") (name "Net-(JP24-Pad18)") (class "Default")
      (node (ref "JP24") (pin "18") (pinfunction "18_18") (pintype "passive"))
      (node (ref "JP25") (pin "18") (pinfunction "18_18") (pintype "passive"))
      (node (ref "S7") (pin "5") (pinfunction "5_5") (pintype "passive"))
    )
    (net (code "54") (name "Net-(Q1-B)") (class "Default")
      (node (ref "Q1") (pin "1") (pinfunction "B_1") (pintype "bidirectional"))
      (node (ref "S3") (pin "4") (pinfunction "4_4") (pintype "passive"))
    )
    (net (code "55") (name "Net-(Q1-C)") (class "Default")
      (node (ref "Q1") (pin "3") (pinfunction "C_3") (pintype "bidirectional"))
      (node (ref "R23") (pin "1") (pinfunction "1_1") (pintype "passive"))
    )
    (net (code "56") (name "Net-(Q2-B)") (class "Default")
      (node (ref "Q2") (pin "1") (pinfunction "B_1") (pintype "bidirectional"))
      (node (ref "S3") (pin "5") (pinfunction "5_5") (pintype "passive"))
    )
    (net (code "57") (name "Net-(Q2-C)") (class "Default")
      (node (ref "Q2") (pin "3") (pinfunction "C_3") (pintype "bidirectional"))
      (node (ref "R24") (pin "1") (pinfunction "1_1") (pintype "passive"))
    )
    (net (code "58") (name "Net-(Q3-B)") (class "Default")
      (node (ref "Q3") (pin "1") (pinfunction "B_1") (pintype "bidirectional"))
      (node (ref "S3") (pin "6") (pinfunction "6_6") (pintype "passive"))
    )
    (net (code "59") (name "Net-(Q3-C)") (class "Default")
      (node (ref "Q3") (pin "3") (pinfunction "C_3") (pintype "bidirectional"))
      (node (ref "R25") (pin "1") (pinfunction "1_1") (pintype "passive"))
    )
    (net (code "60") (name "Net-(R4-PadI1)") (class "Default")
      (node (ref "R4") (pin "I1") (pinfunction "I1_I1") (pintype "bidirectional"))
      (node (ref "S1") (pin "4") (pinfunction "4_4") (pintype "bidirectional"))
    )
    (net (code "61") (name "Net-(R4-PadV1)") (class "Default")
      (node (ref "R4") (pin "V1") (pinfunction "V1_V1") (pintype "bidirectional"))
      (node (ref "S1") (pin "8") (pinfunction "8_8") (pintype "bidirectional"))
    )
    (net (code "62") (name "Net-(R5-Pad2)") (class "Default")
      (node (ref "R5") (pin "2") (pinfunction "2_2") (pintype "passive"))
      (node (ref "S1") (pin "2") (pinfunction "2_2") (pintype "bidirectional"))
      (node (ref "S1") (pin "6") (pinfunction "6_6") (pintype "bidirectional"))
    )
    (net (code "63") (name "Net-(R13-Pad1)") (class "Default")
      (node (ref "R13") (pin "1") (pinfunction "1_1") (pintype "passive"))
      (node (ref "R14") (pin "2") (pinfunction "2_2") (pintype "passive"))
    )
    (net (code "64") (name "Net-(R15-Pad2)") (class "Default")
      (node (ref "R15") (pin "2") (pinfunction "2_2") (pintype "passive"))
      (node (ref "S1") (pin "7") (pinfunction "7_7") (pintype "bidirectional"))
    )
    (net (code "65") (name "Net-(U1-NR)") (class "Default")
      (node (ref "C6") (pin "1") (pinfunction "1_1") (pintype "passive"))
      (node (ref "U1") (pin "7") (pinfunction "NR_7") (pintype "bidirectional"))
    )
    (net (code "66") (name "Net-(U1-SENSE{slash}ADJ)") (class "Default")
      (node (ref "R7") (pin "2") (pinfunction "2_2") (pintype "passive"))
      (node (ref "R8") (pin "1") (pinfunction "1_1") (pintype "passive"))
      (node (ref "U1") (pin "3") (pinfunction "SENSE/ADJ_3") (pintype "bidirectional"))
    )
    (net (code "67") (name "Net-(U2-NR)") (class "Default")
      (node (ref "C8") (pin "1") (pinfunction "1_1") (pintype "passive"))
      (node (ref "U2") (pin "7") (pinfunction "NR_7") (pintype "bidirectional"))
    )
    (net (code "68") (name "Net-(U2-SENSE{slash}ADJ)") (class "Default")
      (node (ref "R10") (pin "2") (pinfunction "2_2") (pintype "passive"))
      (node (ref "R11") (pin "1") (pinfunction "1_1") (pintype "passive"))
      (node (ref "U2") (pin "3") (pinfunction "SENSE/ADJ_3") (pintype "bidirectional"))
    )
    (net (code "69") (name "Net-(U3-NR)") (class "Default")
      (node (ref "C12") (pin "1") (pinfunction "1_1") (pintype "passive"))
      (node (ref "U3") (pin "7") (pinfunction "NR_7") (pintype "bidirectional"))
    )
    (net (code "70") (name "Net-(U3-SENSE{slash}ADJ)") (class "Default")
      (node (ref "R19") (pin "2") (pinfunction "2_2") (pintype "passive"))
      (node (ref "R20") (pin "1") (pinfunction "1_1") (pintype "passive"))
      (node (ref "U3") (pin "3") (pinfunction "SENSE/ADJ_3") (pintype "bidirectional"))
    )
    (net (code "71") (name "Net-(U4-+IN)") (class "Default")
      (node (ref "R1") (pin "1") (pinfunction "1_1") (pintype "passive"))
      (node (ref "R3") (pin "2") (pinfunction "2_2") (pintype "passive"))
      (node (ref "U4") (pin "1") (pinfunction "+IN_1") (pintype "input"))
    )
    (net (code "72") (name "Net-(U4--IN)") (class "Default")
      (node (ref "R2") (pin "1") (pinfunction "1_1") (pintype "passive"))
      (node (ref "U4") (pin "3") (pinfunction "-IN_3") (pintype "input"))
      (node (ref "U4") (pin "4") (pinfunction "OUT_4") (pintype "output"))
    )
    (net (code "73") (name "Net-(U5-+IN)") (class "Default")
      (node (ref "R15") (pin "1") (pinfunction "1_1") (pintype "passive"))
      (node (ref "U5") (pin "3") (pinfunction "+IN_3") (pintype "input"))
    )
    (net (code "74") (name "Net-(U5--IN)") (class "Default")
      (node (ref "R12") (pin "2") (pinfunction "2_2") (pintype "passive"))
      (node (ref "R14") (pin "1") (pinfunction "1_1") (pintype "passive"))
      (node (ref "U5") (pin "2") (pinfunction "-IN_2") (pintype "input"))
    )
    (net (code "75") (name "Net-(U5-OUT)") (class "Default")
      (node (ref "R13") (pin "2") (pinfunction "2_2") (pintype "passive"))
      (node (ref "R21") (pin "1") (pinfunction "1_1") (pintype "passive"))
      (node (ref "U5") (pin "6") (pinfunction "OUT_6") (pintype "output"))
    )
    (net (code "76") (name "Net-(U6-SENSE)") (class "Default")
      (node (ref "S2") (pin "6") (pinfunction "6_6") (pintype "bidirectional"))
      (node (ref "U6") (pin "4") (pinfunction "VDD_4") (pintype "power_in"))
      (node (ref "U6") (pin "5") (pinfunction "SENSE_5") (pintype "input"))
    )
    (net (code "77") (name "Net-(U6-~{RESET})") (class "Default")
      (node (ref "R16") (pin "1") (pinfunction "1_1") (pintype "passive"))
      (node (ref "U6") (pin "3") (pinfunction "~{RESET}_3") (pintype "output"))
    )
    (net (code "78") (name "Net-(U7-D+)") (class "Default")
      (node (ref "R26") (pin "1") (pinfunction "1_1") (pintype "passive"))
      (node (ref "U7") (pin "19") (pinfunction "D+_19") (pintype "bidirectional"))
    )
    (net (code "79") (name "Net-(U7-D-)") (class "Default")
      (node (ref "R27") (pin "1") (pinfunction "1_1") (pintype "passive"))
      (node (ref "U7") (pin "18") (pinfunction "D-_18") (pintype "bidirectional"))
    )
    (net (code "80") (name "Net-(U7-OSC1)") (class "Default")
      (node (ref "U7") (pin "2") (pinfunction "OSC1_2") (pintype "input"))
      (node (ref "Y1") (pin "1") (pinfunction "1_1") (pintype "passive"))
    )
    (net (code "81") (name "Net-(U7-OSC2)") (class "Default")
      (node (ref "U7") (pin "3") (pinfunction "OSC2_3") (pintype "output"))
      (node (ref "Y1") (pin "3") (pinfunction "3_3") (pintype "passive"))
    )
    (net (code "82") (name "Net-(U7-RST*)") (class "Default")
      (node (ref "R28") (pin "2") (pinfunction "2_2") (pintype "passive"))
      (node (ref "U7") (pin "4") (pinfunction "RST*_4") (pintype "input"))
    )
    (net (code "83") (name "Net-(U7-VUSB)") (class "Default")
      (node (ref "C14") (pin "1") (pinfunction "1_1") (pintype "passive"))
      (node (ref "U7") (pin "17") (pinfunction "VUSB_17") (pintype "power_in"))
    )
    (net (code "84") (name "SPI_SCK") (class "Default")
      (node (ref "JP24") (pin "3") (pinfunction "3_3") (pintype "passive"))
      (node (ref "JP25") (pin "3") (pinfunction "3_3") (pintype "passive"))
    )
    (net (code "85") (name "SPI_SDI") (class "Default")
      (node (ref "JP24") (pin "1") (pinfunction "1_1") (pintype "passive"))
      (node (ref "JP25") (pin "1") (pinfunction "1_1") (pintype "passive"))
    )
    (net (code "86") (name "SPI_SDO") (class "Default")
      (node (ref "JP24") (pin "2") (pinfunction "2_2") (pintype "passive"))
      (node (ref "JP25") (pin "2") (pinfunction "2_2") (pintype "passive"))
    )
    (net (code "87") (name "UART1_RX") (class "Default")
      (node (ref "S7") (pin "1") (pinfunction "1_1") (pintype "passive"))
      (node (ref "U7") (pin "10") (pinfunction "TX_10") (pintype "output"))
    )
    (net (code "88") (name "UART1_TX") (class "Default")
      (node (ref "S7") (pin "2") (pinfunction "2_2") (pintype "passive"))
      (node (ref "U7") (pin "12") (pinfunction "RX_12") (pintype "input"))
    )
    (net (code "89") (name "UART2_RX") (class "Default")
      (node (ref "JP24") (pin "20") (pinfunction "20_20") (pintype "passive"))
      (node (ref "JP25") (pin "20") (pinfunction "20_20") (pintype "passive"))
    )
    (net (code "90") (name "UART2_TX") (class "Default")
      (node (ref "JP24") (pin "21") (pinfunction "21_21") (pintype "passive"))
      (node (ref "JP25") (pin "21") (pinfunction "21_21") (pintype "passive"))
    )
    (net (code "91") (name "USER_BTN1") (class "Default")
      (node (ref "JP22") (pin "18") (pinfunction "18_18") (pintype "passive"))
      (node (ref "JP23") (pin "18") (pinfunction "18_18") (pintype "passive"))
      (node (ref "S4") (pin "3") (pintype "bidirectional"))
      (node (ref "S4") (pin "4") (pintype "bidirectional"))
    )
    (net (code "92") (name "USER_BTN2") (class "Default")
      (node (ref "JP22") (pin "19") (pinfunction "19_19") (pintype "passive"))
      (node (ref "JP23") (pin "19") (pinfunction "19_19") (pintype "passive"))
      (node (ref "S5") (pin "3") (pintype "bidirectional"))
      (node (ref "S5") (pin "4") (pintype "bidirectional"))
    )
    (net (code "93") (name "USER_BTN3") (class "Default")
      (node (ref "JP22") (pin "20") (pinfunction "20_20") (pintype "passive"))
      (node (ref "JP23") (pin "20") (pinfunction "20_20") (pintype "passive"))
      (node (ref "S6") (pin "3") (pintype "bidirectional"))
      (node (ref "S6") (pin "4") (pintype "bidirectional"))
    )
    (net (code "94") (name "USER_LED1") (class "Default")
      (node (ref "JP22") (pin "13") (pinfunction "13_13") (pintype "passive"))
      (node (ref "JP23") (pin "13") (pinfunction "13_13") (pintype "passive"))
      (node (ref "S3") (pin "3") (pinfunction "3_3") (pintype "passive"))
    )
    (net (code "95") (name "USER_LED2") (class "Default")
      (node (ref "JP22") (pin "14") (pinfunction "14_14") (pintype "passive"))
      (node (ref "JP23") (pin "14") (pinfunction "14_14") (pintype "passive"))
      (node (ref "S3") (pin "2") (pinfunction "2_2") (pintype "passive"))
    )
    (net (code "96") (name "USER_LED3") (class "Default")
      (node (ref "JP22") (pin "15") (pinfunction "15_15") (pintype "passive"))
      (node (ref "JP23") (pin "15") (pinfunction "15_15") (pintype "passive"))
      (node (ref "S3") (pin "1") (pinfunction "1_1") (pintype "passive"))
    )
    (net (code "97") (name "V+") (class "Default")
      (node (ref "C10") (pin "1") (pinfunction "1_1") (pintype "passive"))
      (node (ref "C5") (pin "1") (pinfunction "1_1") (pintype "passive"))
      (node (ref "R1") (pin "2") (pinfunction "2_2") (pintype "passive"))
      (node (ref "S2") (pin "2") (pinfunction "2_2") (pintype "bidirectional"))
      (node (ref "S2") (pin "4") (pinfunction "4_4") (pintype "bidirectional"))
      (node (ref "U4") (pin "5") (pinfunction "V+_5") (pintype "power_in"))
      (node (ref "U5") (pin "1") (pinfunction "~{SHUTDOWN}_1") (pintype "passive"))
      (node (ref "U5") (pin "7") (pinfunction "V+_7") (pintype "power_in"))
    )
    (net (code "98") (name "V-") (class "Default")
      (node (ref "C11") (pin "1") (pinfunction "1_1") (pintype "passive"))
      (node (ref "C5") (pin "2") (pinfunction "2_2") (pintype "passive"))
      (node (ref "D2") (pin "C") (pinfunction "C_C") (pintype "passive"))
      (node (ref "JP18") (pin "-") (pinfunction "-_-") (pintype "passive"))
      (node (ref "R3") (pin "1") (pinfunction "1_1") (pintype "passive"))
      (node (ref "U4") (pin "2") (pinfunction "V-_2") (pintype "power_in"))
      (node (ref "U5") (pin "4") (pinfunction "V-_4") (pintype "power_in"))
      (node (ref "U6") (pin "2") (pinfunction "GND_2") (pintype "power_in"))
    )
    (net (code "99") (name "VGND") (class "Default")
      (node (ref "C10") (pin "2") (pinfunction "2_2") (pintype "passive"))
      (node (ref "C11") (pin "2") (pinfunction "2_2") (pintype "passive"))
      (node (ref "JP20") (pin "2") (pinfunction "2_2") (pintype "passive"))
      (node (ref "JP21") (pin "P$1") (pinfunction "1_P$1") (pintype "passive"))
      (node (ref "R12") (pin "1") (pinfunction "1_1") (pintype "passive"))
      (node (ref "R2") (pin "2") (pinfunction "2_2") (pintype "passive"))
      (node (ref "R4") (pin "V2") (pinfunction "V2_V2") (pintype "bidirectional"))
    )
    (net (code "100") (name "VUSB") (class "Default")
      (node (ref "C13") (pin "1") (pinfunction "1_1") (pintype "passive"))
      (node (ref "C17") (pin "1") (pinfunction "1_1") (pintype "passive"))
      (node (ref "L1") (pin "1") (pinfunction "1_1") (pintype "passive"))
      (node (ref "R29") (pin "2") (pinfunction "2_2") (pintype "passive"))
      (node (ref "U7") (pin "1") (pinfunction "VDD_1") (pintype "power_in"))
      (node (ref "U8") (pin "5") (pinfunction "VCC_5") (pintype "power_in"))
    )
    (net (code "101") (name "V_EXT") (class "Default")
      (node (ref "JP16") (pin "1") (pinfunction "1_1") (pintype "passive"))
      (node (ref "JP16") (pin "2") (pinfunction "2_2") (pintype "passive"))
      (node (ref "JP16") (pin "3") (pinfunction "3_3") (pintype "passive"))
      (node (ref "JP16") (pin "4") (pinfunction "4_4") (pintype "passive"))
      (node (ref "JP3") (pin "P$1") (pinfunction "1_P$1") (pintype "passive"))
      (node (ref "JP4") (pin "1") (pinfunction "1_1") (pintype "passive"))
    )
    (net (code "102") (name "unconnected-(JP27-PadID)") (class "Default")
      (node (ref "JP27") (pin "ID") (pinfunction "ID_ID") (pintype "bidirectional"))
    )
    (net (code "103") (name "unconnected-(S1-Pad1)") (class "Default")
      (node (ref "S1") (pin "1") (pinfunction "1_1") (pintype "bidirectional"))
    )
    (net (code "104") (name "unconnected-(S2-Pad1)") (class "Default")
      (node (ref "S2") (pin "1") (pinfunction "1_1") (pintype "bidirectional"))
    )
    (net (code "105") (name "unconnected-(S2-Pad5)") (class "Default")
      (node (ref "S2") (pin "5") (pinfunction "5_5") (pintype "bidirectional"))
    )
    (net (code "106") (name "unconnected-(S2-Pad8)") (class "Default")
      (node (ref "S2") (pin "8") (pinfunction "8_8") (pintype "bidirectional"))
    )
    (net (code "107") (name "unconnected-(U1-PWRG-Pad5)") (class "Default")
      (node (ref "U1") (pin "5") (pinfunction "PWRG_5") (pintype "bidirectional"))
    )
    (net (code "108") (name "unconnected-(U2-PWRG-Pad5)") (class "Default")
      (node (ref "U2") (pin "5") (pinfunction "PWRG_5") (pintype "bidirectional"))
    )
    (net (code "109") (name "unconnected-(U3-PWRG-Pad5)") (class "Default")
      (node (ref "U3") (pin "5") (pinfunction "PWRG_5") (pintype "bidirectional"))
    )
    (net (code "110") (name "unconnected-(U7-GP0{slash}SSPND-Pad16)") (class "Default")
      (node (ref "U7") (pin "16") (pinfunction "GP0/SSPND_16") (pintype "bidirectional"))
    )
    (net (code "111") (name "unconnected-(U7-GP1{slash}USBCFG-Pad15)") (class "Default")
      (node (ref "U7") (pin "15") (pinfunction "GP1/USBCFG_15") (pintype "bidirectional"))
    )
    (net (code "112") (name "unconnected-(U7-GP2-Pad14)") (class "Default")
      (node (ref "U7") (pin "14") (pinfunction "GP2_14") (pintype "bidirectional"))
    )
    (net (code "113") (name "unconnected-(U7-GP3-Pad9)") (class "Default")
      (node (ref "U7") (pin "9") (pinfunction "GP3_9") (pintype "bidirectional"))
    )
    (net (code "114") (name "unconnected-(U7-GP4-Pad8)") (class "Default")
      (node (ref "U7") (pin "8") (pinfunction "GP4_8") (pintype "bidirectional"))
    )
    (net (code "115") (name "unconnected-(U7-GP5-Pad7)") (class "Default")
      (node (ref "U7") (pin "7") (pinfunction "GP5_7") (pintype "bidirectional"))
    )
    (net (code "116") (name "unconnected-(U7-GP6{slash}RXLED-Pad6)") (class "Default")
      (node (ref "U7") (pin "6") (pinfunction "GP6/RXLED_6") (pintype "bidirectional"))
    )
    (net (code "117") (name "unconnected-(U7-GP7{slash}TXLED-Pad5)") (class "Default")
      (node (ref "U7") (pin "5") (pinfunction "GP7/TXLED_5") (pintype "bidirectional"))
    )
    (net (code "118") (name "unconnected-(U8-IO3-Pad4)") (class "Default")
      (node (ref "U8") (pin "4") (pinfunction "IO3_4") (pintype "bidirectional"))
    )
    (net (code "119") (name "~{SPI_SS}") (class "Default")
      (node (ref "JP24") (pin "4") (pinfunction "4_4") (pintype "passive"))
      (node (ref "JP25") (pin "4") (pinfunction "4_4") (pintype "passive"))
    )
    (net (code "120") (name "~{UART1_CTS}") (class "Default")
      (node (ref "S7") (pin "4") (pinfunction "4_4") (pintype "passive"))
      (node (ref "U7") (pin "11") (pinfunction "RTS*_11") (pintype "output"))
    )
    (net (code "121") (name "~{UART1_RTS}") (class "Default")
      (node (ref "S7") (pin "3") (pinfunction "3_3") (pintype "passive"))
      (node (ref "U7") (pin "13") (pinfunction "CTS*_13") (pintype "input"))
    )
    (net (code "122") (name "~{UART2_CTS}") (class "Default")
      (node (ref "JP24") (pin "23") (pinfunction "23_23") (pintype "passive"))
      (node (ref "JP25") (pin "23") (pinfunction "23_23") (pintype "passive"))
    )
    (net (code "123") (name "~{UART2_RTS}") (class "Default")
      (node (ref "JP24") (pin "22") (pinfunction "22_22") (pintype "passive"))
      (node (ref "JP25") (pin "22") (pinfunction "22_22") (pintype "passive"))
    )
  )
)
